# slush_cap_board_rev_d.net
KiCad netlist of a schematic drawn in EAGLE
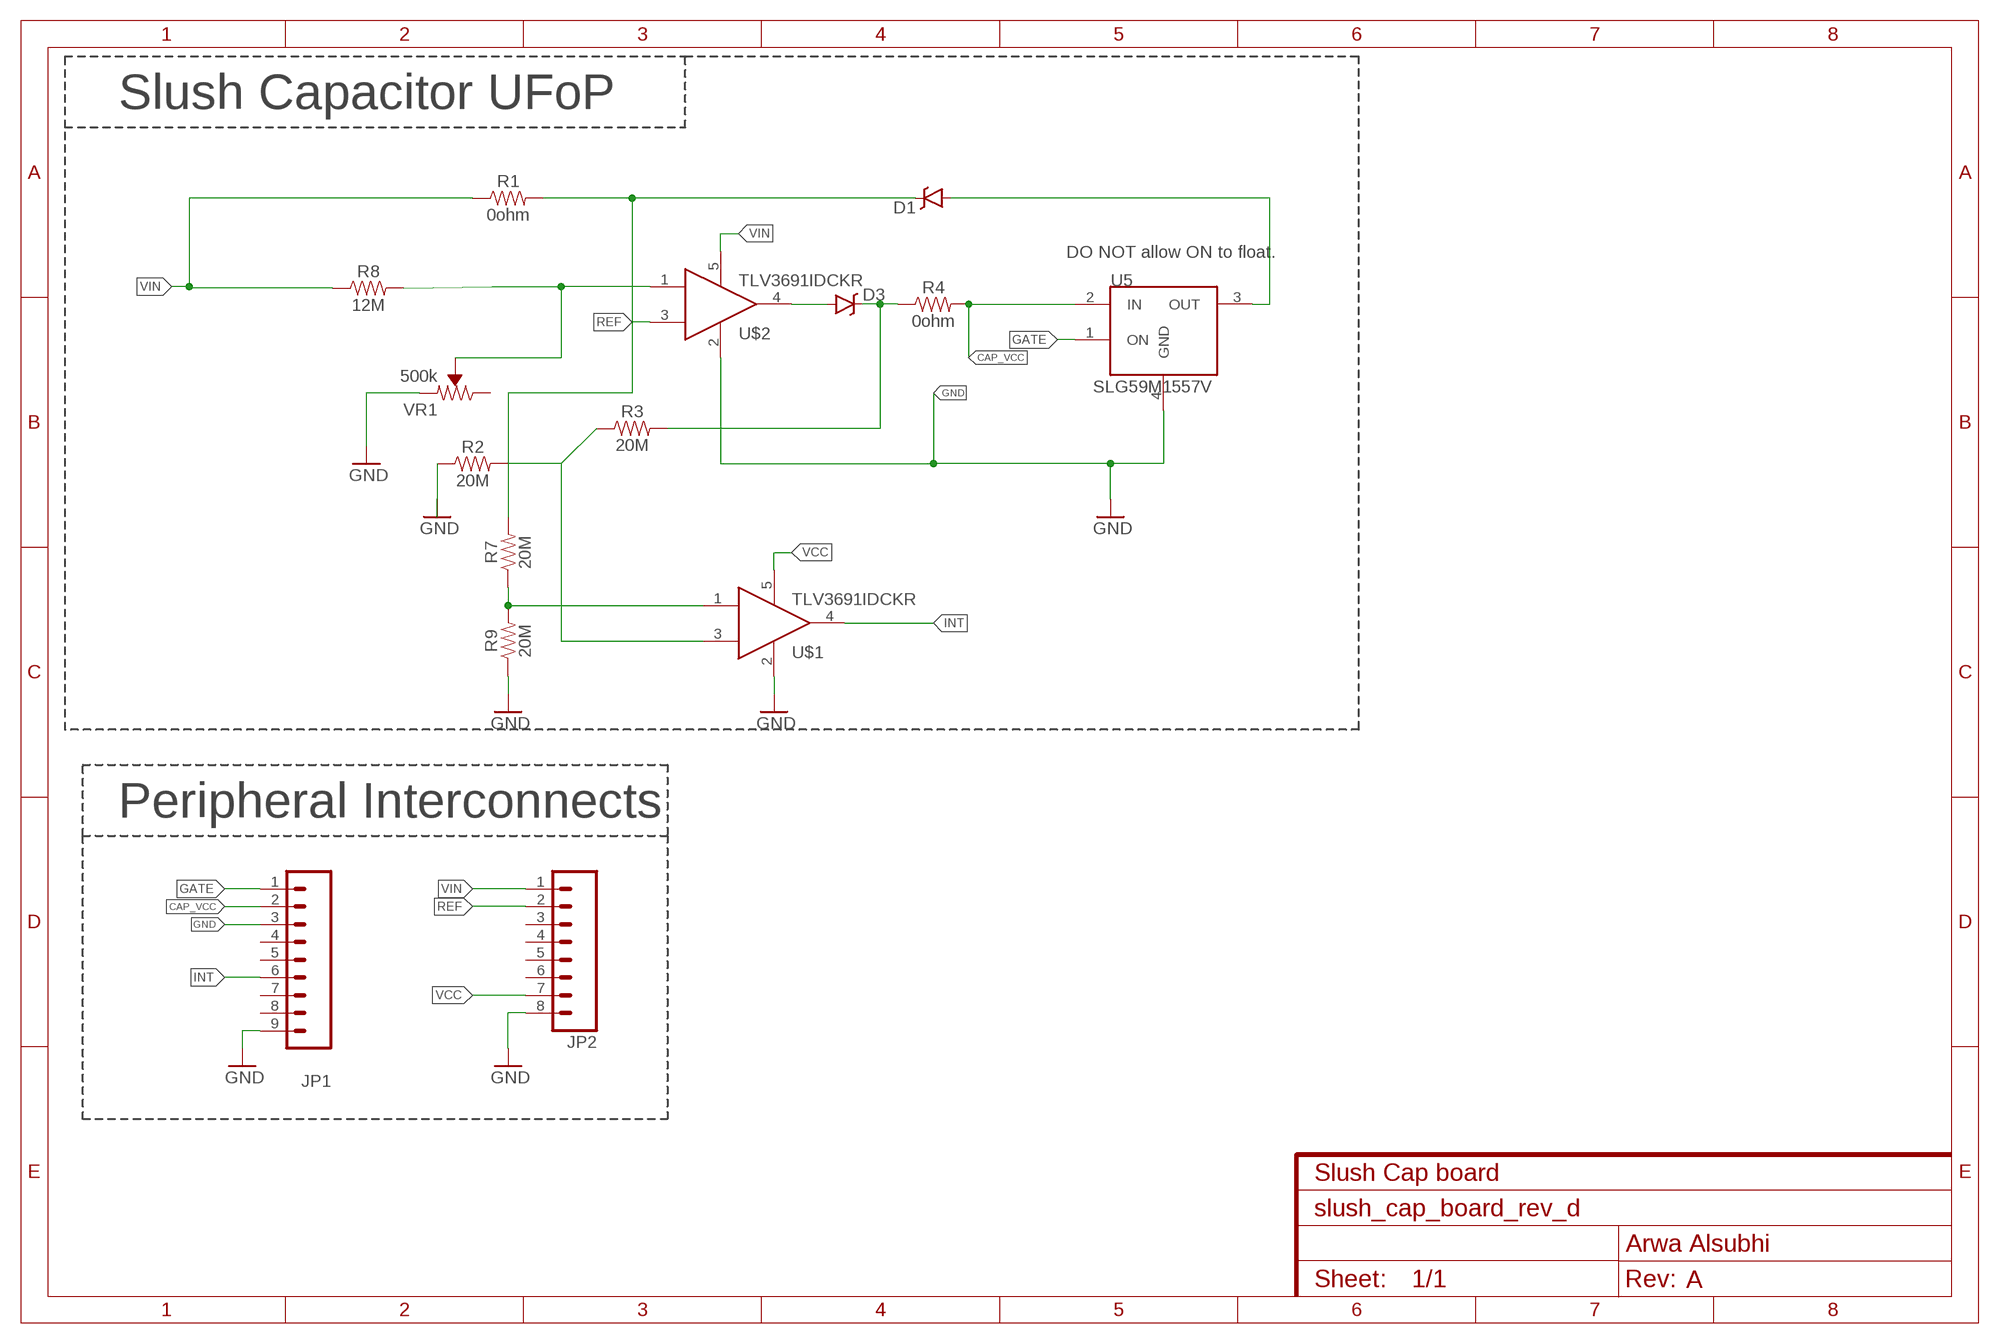
[diagram p0: schematic, sheet 1]

(export (version "E")
  (design (tool "Eeschema 10.0.6"))
  (components
    (comp (ref "D1")
      (value "RB751")
      (footprint "eagle-import:SOD-523")
      (fields (field (name "MPN") "BAS40-02V-V-G-08"))
      (libsource (lib "eagle-import") (part "DIODE-SCHOTTKY-RB751"))
    )
    (comp (ref "D3")
      (value "RB751")
      (footprint "eagle-import:SOD-523")
      (fields (field (name "MPN") "BAS40-02V-V-G-08"))
      (libsource (lib "eagle-import") (part "DIODE-SCHOTTKY-RB751"))
    )
    (comp (ref "JP1")
      (value "M091.27MM")
      (footprint "eagle-import:1X09-1.27MM")
      (fields (field (name "MANUFACTURERPARTNUMBER") "GRPB091VWVN-RC ") (field (name "MPN") "GRPB091VWVN-RC"))
      (libsource (lib "eagle-import") (part "M091.27MM"))
    )
    (comp (ref "JP2")
      (value "M081.27MM")
      (footprint "eagle-import:1X08-1.27MM")
      (fields (field (name "MANUFACTURERPARTNUMBER") "GRPB081VWVN-RC "))
      (libsource (lib "eagle-import") (part "M081.27MM"))
    )
    (comp (ref "R1")
      (value "0ohm")
      (footprint "eagle-import:0603")
      (libsource (lib "eagle-import") (part "0603-RESISTOR-0603-1/10W-1%"))
    )
    (comp (ref "R2")
      (value "20M")
      (footprint "eagle-import:0805")
      (libsource (lib "eagle-import") (part "0.3OHM-0805-1/8W-1%"))
    )
    (comp (ref "R3")
      (value "20M")
      (footprint "eagle-import:0805")
      (libsource (lib "eagle-import") (part "0.3OHM-0805-1/8W-1%"))
    )
    (comp (ref "R4")
      (value "0ohm")
      (footprint "eagle-import:0603")
      (libsource (lib "eagle-import") (part "0603-RESISTOR-0603-1/10W-1%"))
    )
    (comp (ref "R7")
      (value "20M")
      (footprint "eagle-import:0805")
      (libsource (lib "eagle-import") (part "0.3OHM-0805-1/8W-1%"))
    )
    (comp (ref "R8")
      (value "12M")
      (footprint "eagle-import:0805")
      (libsource (lib "eagle-import") (part "0.3OHM-0805-1/8W-1%"))
    )
    (comp (ref "R9")
      (value "20M")
      (footprint "eagle-import:0805")
      (libsource (lib "eagle-import") (part "0.3OHM-0805-1/8W-1%"))
    )
    (comp (ref "U$1")
      (value "TLV3691IDCKR")
      (footprint "eagle-import:SOT353")
      (libsource (lib "eagle-import") (part "TLV3691IDCKR"))
    )
    (comp (ref "U$2")
      (value "TLV3691IDCKR")
      (footprint "eagle-import:SOT353")
      (libsource (lib "eagle-import") (part "TLV3691IDCKR"))
    )
    (comp (ref "U5")
      (value "SLG59M1557V")
      (footprint "eagle-import:4STDFN")
      (fields (field (name "MPN") "SLG59M1557V "))
      (libsource (lib "eagle-import") (part "SLG59M1557V"))
    )
    (comp (ref "VR1")
      (value "500k")
      (footprint "eagle-import:TRIMPOT-SMD-3MM-CLOSED")
      (libsource (lib "eagle-import") (part "TRIMPOT-SMD-3MM-CLOSED-1/8W-20%"))
    )
  )
  (nets
    (net (code "1") (name "CAP_VCC") (class "Default")
      (node (ref "JP1") (pin "2") (pinfunction "2_2") (pintype "passive"))
      (node (ref "R4") (pin "2") (pinfunction "2_2") (pintype "passive"))
      (node (ref "U5") (pin "2") (pinfunction "IN_2") (pintype "bidirectional"))
    )
    (net (code "2") (name "GATE") (class "Default")
      (node (ref "JP1") (pin "1") (pinfunction "1_1") (pintype "passive"))
      (node (ref "U5") (pin "1") (pinfunction "ON_1") (pintype "bidirectional"))
    )
    (net (code "3") (name "GND") (class "Default")
      (node (ref "JP1") (pin "3") (pinfunction "3_3") (pintype "passive"))
      (node (ref "JP1") (pin "9") (pinfunction "9_9") (pintype "passive"))
      (node (ref "JP2") (pin "8") (pinfunction "8_8") (pintype "passive"))
      (node (ref "R2") (pin "1") (pinfunction "1_1") (pintype "passive"))
      (node (ref "R9") (pin "1") (pinfunction "1_1") (pintype "passive"))
      (node (ref "U$1") (pin "2") (pinfunction "2_2") (pintype "bidirectional"))
      (node (ref "U$2") (pin "2") (pinfunction "2_2") (pintype "bidirectional"))
      (node (ref "U5") (pin "4") (pinfunction "GND_4") (pintype "bidirectional"))
      (node (ref "VR1") (pin "1") (pinfunction "CCW_1") (pintype "passive"))
    )
    (net (code "4") (name "INT") (class "Default")
      (node (ref "JP1") (pin "6") (pinfunction "6_6") (pintype "passive"))
      (node (ref "U$1") (pin "4") (pinfunction "4_4") (pintype "bidirectional"))
    )
    (net (code "5") (name "Net-(D1-PadC)") (class "Default")
      (node (ref "D1") (pin "C") (pinfunction "C_C") (pintype "passive"))
      (node (ref "R1") (pin "2") (pinfunction "2_2") (pintype "passive"))
      (node (ref "R7") (pin "2") (pinfunction "2_2") (pintype "passive"))
    )
    (net (code "6") (name "Net-(D3-PadA)") (class "Default")
      (node (ref "D3") (pin "A") (pinfunction "A_A") (pintype "passive"))
      (node (ref "U$2") (pin "4") (pinfunction "4_4") (pintype "bidirectional"))
    )
    (net (code "7") (name "Net-(D3-PadC)") (class "Default")
      (node (ref "D3") (pin "C") (pinfunction "C_C") (pintype "passive"))
      (node (ref "R3") (pin "2") (pinfunction "2_2") (pintype "passive"))
      (node (ref "R4") (pin "1") (pinfunction "1_1") (pintype "passive"))
    )
    (net (code "8") (name "Net-(R2-Pad2)") (class "Default")
      (node (ref "R2") (pin "2") (pinfunction "2_2") (pintype "passive"))
      (node (ref "R3") (pin "1") (pinfunction "1_1") (pintype "passive"))
      (node (ref "U$1") (pin "3") (pinfunction "3_3") (pintype "bidirectional"))
    )
    (net (code "9") (name "Net-(R7-Pad1)") (class "Default")
      (node (ref "R7") (pin "1") (pinfunction "1_1") (pintype "passive"))
      (node (ref "R9") (pin "2") (pinfunction "2_2") (pintype "passive"))
      (node (ref "U$1") (pin "1") (pinfunction "1_1") (pintype "bidirectional"))
    )
    (net (code "10") (name "Net-(U5-OUT)") (class "Default")
      (node (ref "D1") (pin "A") (pinfunction "A_A") (pintype "passive"))
      (node (ref "U5") (pin "3") (pinfunction "OUT_3") (pintype "bidirectional"))
    )
    (net (code "11") (name "Net-(VR1-WIPER)") (class "Default")
      (node (ref "R8") (pin "2") (pinfunction "2_2") (pintype "passive"))
      (node (ref "U$2") (pin "1") (pinfunction "1_1") (pintype "bidirectional"))
      (node (ref "VR1") (pin "2") (pinfunction "WIPER_2") (pintype "passive"))
    )
    (net (code "12") (name "REF") (class "Default")
      (node (ref "JP2") (pin "2") (pinfunction "2_2") (pintype "passive"))
      (node (ref "U$2") (pin "3") (pinfunction "3_3") (pintype "bidirectional"))
    )
    (net (code "13") (name "VCC") (class "Default")
      (node (ref "JP2") (pin "7") (pinfunction "7_7") (pintype "passive"))
      (node (ref "U$1") (pin "5") (pinfunction "5_5") (pintype "bidirectional"))
    )
    (net (code "14") (name "VIN") (class "Default")
      (node (ref "JP2") (pin "1") (pinfunction "1_1") (pintype "passive"))
      (node (ref "R1") (pin "1") (pinfunction "1_1") (pintype "passive"))
      (node (ref "R8") (pin "1") (pinfunction "1_1") (pintype "passive"))
      (node (ref "U$2") (pin "5") (pinfunction "5_5") (pintype "bidirectional"))
    )
    (net (code "15") (name "unconnected-(JP1-Pad4)") (class "Default")
      (node (ref "JP1") (pin "4") (pinfunction "4_4") (pintype "passive"))
    )
    (net (code "16") (name "unconnected-(JP1-Pad5)") (class "Default")
      (node (ref "JP1") (pin "5") (pinfunction "5_5") (pintype "passive"))
    )
    (net (code "17") (name "unconnected-(JP1-Pad7)") (class "Default")
      (node (ref "JP1") (pin "7") (pinfunction "7_7") (pintype "passive"))
    )
    (net (code "18") (name "unconnected-(JP1-Pad8)") (class "Default")
      (node (ref "JP1") (pin "8") (pinfunction "8_8") (pintype "passive"))
    )
    (net (code "19") (name "unconnected-(JP2-Pad3)") (class "Default")
      (node (ref "JP2") (pin "3") (pinfunction "3_3") (pintype "passive"))
    )
    (net (code "20") (name "unconnected-(JP2-Pad4)") (class "Default")
      (node (ref "JP2") (pin "4") (pinfunction "4_4") (pintype "passive"))
    )
    (net (code "21") (name "unconnected-(JP2-Pad5)") (class "Default")
      (node (ref "JP2") (pin "5") (pinfunction "5_5") (pintype "passive"))
    )
    (net (code "22") (name "unconnected-(JP2-Pad6)") (class "Default")
      (node (ref "JP2") (pin "6") (pinfunction "6_6") (pintype "passive"))
    )
    (net (code "23") (name "unconnected-(VR1-CW-Pad3)") (class "Default")
      (node (ref "VR1") (pin "3") (pinfunction "CW_3") (pintype "passive"))
    )
  )
)
